# BDAN_ACOND.net
KiCad netlist of a schematic drawn in Altium Designer
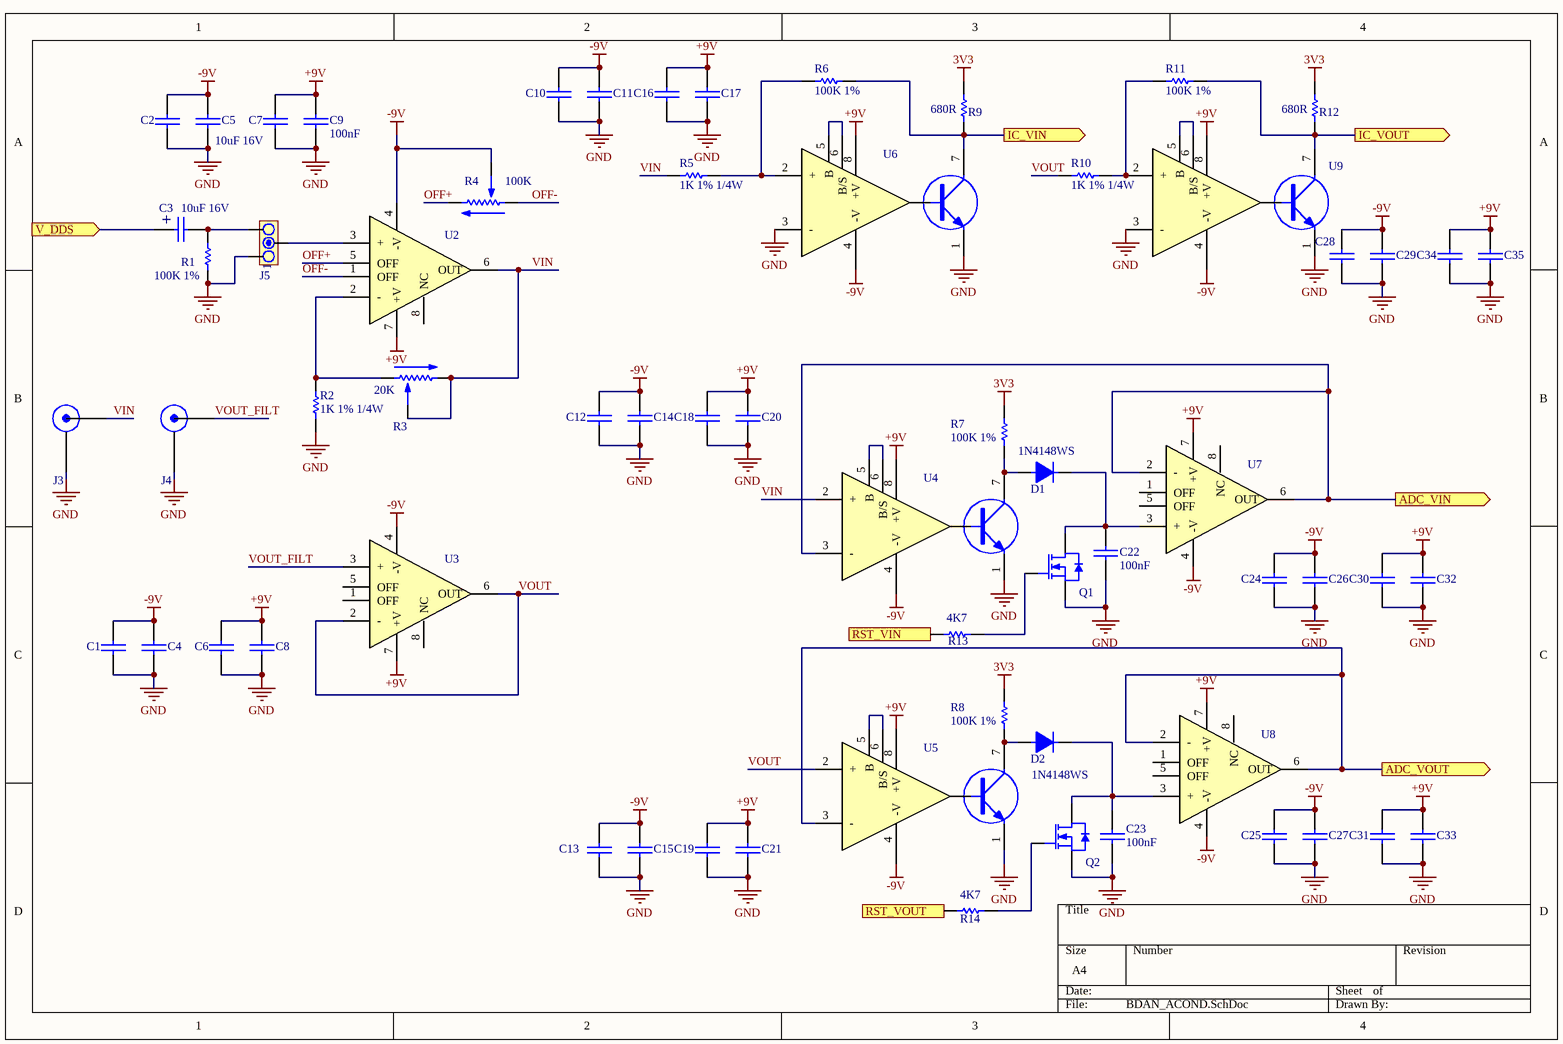
[diagram p0: BDAN_ACOND.SchDoc]

(export (version "E")
  (design (tool "Eeschema 10.0.6"))
  (components
    (comp (ref "C1")
      (value "100nF")
      (footprint "0805")
      (description "CAP0805 100nF X7R")
      (fields (field (name "PART NUMBER") "CAP0805_100nF_X7R"))
      (libsource (lib "gl_LIB") (part "CAP"))
    )
    (comp (ref "C2")
      (value "100nF")
      (footprint "0805")
      (description "CAP0805 100nF X7R")
      (fields (field (name "PART NUMBER") "CAP0805_100nF_X7R"))
      (libsource (lib "gl_LIB") (part "CAP"))
    )
    (comp (ref "C3")
      (value "10uF 16V")
      (footprint "CAP318")
      (description "CAP TANT 10UF 10% 16V RADIAL")
      (fields
        (field (name "PART NUMBER") "CAP_TAN_10uF_16V_CAP318")
        (field (name "MANUFACTURER") "KYOCERA AVX")
      )
      (libsource (lib "gl_LIB") (part "CAPPOL"))
    )
    (comp (ref "C4")
      (value "10uF 16V")
      (footprint "0805")
      (description "CAP0805 10uF 16V X5R")
      (fields
        (field (name "PART NUMBER") "CAP0805_10uF_16V_X5R")
        (field (name "MANUFACTURER") "TDK Corporation")
      )
      (libsource (lib "gl_LIB") (part "CAP"))
    )
    (comp (ref "C5")
      (value "10uF 16V")
      (footprint "0805")
      (description "CAP0805 10uF 16V X5R")
      (fields
        (field (name "PART NUMBER") "CAP0805_10uF_16V_X5R")
        (field (name "MANUFACTURER") "TDK Corporation")
      )
      (libsource (lib "gl_LIB") (part "CAP"))
    )
    (comp (ref "C6")
      (value "10uF 16V")
      (footprint "0805")
      (description "CAP0805 10uF 16V X5R")
      (fields
        (field (name "PART NUMBER") "CAP0805_10uF_16V_X5R")
        (field (name "MANUFACTURER") "TDK Corporation")
      )
      (libsource (lib "gl_LIB") (part "CAP"))
    )
    (comp (ref "C7")
      (value "10uF 16V")
      (footprint "0805")
      (description "CAP0805 10uF 16V X5R")
      (fields
        (field (name "PART NUMBER") "CAP0805_10uF_16V_X5R")
        (field (name "MANUFACTURER") "TDK Corporation")
      )
      (libsource (lib "gl_LIB") (part "CAP"))
    )
    (comp (ref "C8")
      (value "100nF")
      (footprint "0805")
      (description "CAP0805 100nF X7R")
      (fields (field (name "PART NUMBER") "CAP0805_100nF_X7R"))
      (libsource (lib "gl_LIB") (part "CAP"))
    )
    (comp (ref "C9")
      (value "100nF")
      (footprint "0805")
      (description "CAP0805 100nF X7R")
      (fields (field (name "PART NUMBER") "CAP0805_100nF_X7R"))
      (libsource (lib "gl_LIB") (part "CAP"))
    )
    (comp (ref "C10")
      (value "100nF")
      (footprint "0805")
      (description "CAP0805 100nF X7R")
      (fields (field (name "PART NUMBER") "CAP0805_100nF_X7R"))
      (libsource (lib "gl_LIB") (part "CAP"))
    )
    (comp (ref "C11")
      (value "10uF 16V")
      (footprint "0805")
      (description "CAP0805 10uF 16V X5R")
      (fields
        (field (name "PART NUMBER") "CAP0805_10uF_16V_X5R")
        (field (name "MANUFACTURER") "TDK Corporation")
      )
      (libsource (lib "gl_LIB") (part "CAP"))
    )
    (comp (ref "C12")
      (value "100nF")
      (footprint "0805")
      (description "CAP0805 100nF X7R")
      (fields (field (name "PART NUMBER") "CAP0805_100nF_X7R"))
      (libsource (lib "gl_LIB") (part "CAP"))
    )
    (comp (ref "C13")
      (value "100nF")
      (footprint "0805")
      (description "CAP0805 100nF X7R")
      (fields (field (name "PART NUMBER") "CAP0805_100nF_X7R"))
      (libsource (lib "gl_LIB") (part "CAP"))
    )
    (comp (ref "C14")
      (value "10uF 16V")
      (footprint "0805")
      (description "CAP0805 10uF 16V X5R")
      (fields
        (field (name "PART NUMBER") "CAP0805_10uF_16V_X5R")
        (field (name "MANUFACTURER") "TDK Corporation")
      )
      (libsource (lib "gl_LIB") (part "CAP"))
    )
    (comp (ref "C15")
      (value "10uF 16V")
      (footprint "0805")
      (description "CAP0805 10uF 16V X5R")
      (fields
        (field (name "PART NUMBER") "CAP0805_10uF_16V_X5R")
        (field (name "MANUFACTURER") "TDK Corporation")
      )
      (libsource (lib "gl_LIB") (part "CAP"))
    )
    (comp (ref "C16")
      (value "10uF 16V")
      (footprint "0805")
      (description "CAP0805 10uF 16V X5R")
      (fields
        (field (name "PART NUMBER") "CAP0805_10uF_16V_X5R")
        (field (name "MANUFACTURER") "TDK Corporation")
      )
      (libsource (lib "gl_LIB") (part "CAP"))
    )
    (comp (ref "C17")
      (value "100nF")
      (footprint "0805")
      (description "CAP0805 100nF X7R")
      (fields (field (name "PART NUMBER") "CAP0805_100nF_X7R"))
      (libsource (lib "gl_LIB") (part "CAP"))
    )
    (comp (ref "C18")
      (value "10uF 16V")
      (footprint "0805")
      (description "CAP0805 10uF 16V X5R")
      (fields
        (field (name "PART NUMBER") "CAP0805_10uF_16V_X5R")
        (field (name "MANUFACTURER") "TDK Corporation")
      )
      (libsource (lib "gl_LIB") (part "CAP"))
    )
    (comp (ref "C19")
      (value "10uF 16V")
      (footprint "0805")
      (description "CAP0805 10uF 16V X5R")
      (fields
        (field (name "PART NUMBER") "CAP0805_10uF_16V_X5R")
        (field (name "MANUFACTURER") "TDK Corporation")
      )
      (libsource (lib "gl_LIB") (part "CAP"))
    )
    (comp (ref "C20")
      (value "100nF")
      (footprint "0805")
      (description "CAP0805 100nF X7R")
      (fields (field (name "PART NUMBER") "CAP0805_100nF_X7R"))
      (libsource (lib "gl_LIB") (part "CAP"))
    )
    (comp (ref "C21")
      (value "100nF")
      (footprint "0805")
      (description "CAP0805 100nF X7R")
      (fields (field (name "PART NUMBER") "CAP0805_100nF_X7R"))
      (libsource (lib "gl_LIB") (part "CAP"))
    )
    (comp (ref "C22")
      (value "100nF")
      (footprint "CAP508")
      (description "CAP CER RAD 100NF 250V C0G 10%")
      (fields (field (name "PART NUMBER") "CAP_CER_100nF_250V_CAP508"))
      (libsource (lib "gl_LIB") (part "CAP"))
    )
    (comp (ref "C23")
      (value "100nF")
      (footprint "CAP508")
      (description "CAP CER RAD 100NF 250V C0G 10%")
      (fields (field (name "PART NUMBER") "CAP_CER_100nF_250V_CAP508"))
      (libsource (lib "gl_LIB") (part "CAP"))
    )
    (comp (ref "C24")
      (value "100nF")
      (footprint "0805")
      (description "CAP0805 100nF X7R")
      (fields (field (name "PART NUMBER") "CAP0805_100nF_X7R"))
      (libsource (lib "gl_LIB") (part "CAP"))
    )
    (comp (ref "C25")
      (value "100nF")
      (footprint "0805")
      (description "CAP0805 100nF X7R")
      (fields (field (name "PART NUMBER") "CAP0805_100nF_X7R"))
      (libsource (lib "gl_LIB") (part "CAP"))
    )
    (comp (ref "C26")
      (value "10uF 16V")
      (footprint "0805")
      (description "CAP0805 10uF 16V X5R")
      (fields
        (field (name "PART NUMBER") "CAP0805_10uF_16V_X5R")
        (field (name "MANUFACTURER") "TDK Corporation")
      )
      (libsource (lib "gl_LIB") (part "CAP"))
    )
    (comp (ref "C27")
      (value "10uF 16V")
      (footprint "0805")
      (description "CAP0805 10uF 16V X5R")
      (fields
        (field (name "PART NUMBER") "CAP0805_10uF_16V_X5R")
        (field (name "MANUFACTURER") "TDK Corporation")
      )
      (libsource (lib "gl_LIB") (part "CAP"))
    )
    (comp (ref "C28")
      (value "100nF")
      (footprint "0805")
      (description "CAP0805 100nF X7R")
      (fields (field (name "PART NUMBER") "CAP0805_100nF_X7R"))
      (libsource (lib "gl_LIB") (part "CAP"))
    )
    (comp (ref "C29")
      (value "10uF 16V")
      (footprint "0805")
      (description "CAP0805 10uF 16V X5R")
      (fields
        (field (name "PART NUMBER") "CAP0805_10uF_16V_X5R")
        (field (name "MANUFACTURER") "TDK Corporation")
      )
      (libsource (lib "gl_LIB") (part "CAP"))
    )
    (comp (ref "C30")
      (value "10uF 16V")
      (footprint "0805")
      (description "CAP0805 10uF 16V X5R")
      (fields
        (field (name "PART NUMBER") "CAP0805_10uF_16V_X5R")
        (field (name "MANUFACTURER") "TDK Corporation")
      )
      (libsource (lib "gl_LIB") (part "CAP"))
    )
    (comp (ref "C31")
      (value "10uF 16V")
      (footprint "0805")
      (description "CAP0805 10uF 16V X5R")
      (fields
        (field (name "PART NUMBER") "CAP0805_10uF_16V_X5R")
        (field (name "MANUFACTURER") "TDK Corporation")
      )
      (libsource (lib "gl_LIB") (part "CAP"))
    )
    (comp (ref "C32")
      (value "100nF")
      (footprint "0805")
      (description "CAP0805 100nF X7R")
      (fields (field (name "PART NUMBER") "CAP0805_100nF_X7R"))
      (libsource (lib "gl_LIB") (part "CAP"))
    )
    (comp (ref "C33")
      (value "100nF")
      (footprint "0805")
      (description "CAP0805 100nF X7R")
      (fields (field (name "PART NUMBER") "CAP0805_100nF_X7R"))
      (libsource (lib "gl_LIB") (part "CAP"))
    )
    (comp (ref "C34")
      (value "10uF 16V")
      (footprint "0805")
      (description "CAP0805 10uF 16V X5R")
      (fields
        (field (name "PART NUMBER") "CAP0805_10uF_16V_X5R")
        (field (name "MANUFACTURER") "TDK Corporation")
      )
      (libsource (lib "gl_LIB") (part "CAP"))
    )
    (comp (ref "C35")
      (value "100nF")
      (footprint "0805")
      (description "CAP0805 100nF X7R")
      (fields (field (name "PART NUMBER") "CAP0805_100nF_X7R"))
      (libsource (lib "gl_LIB") (part "CAP"))
    )
    (comp (ref "D1")
      (value "1N4148WS")
      (footprint "SOD323F")
      (description "DIODE 75V 150MA SOD323F")
      (fields (field (name "PART NUMBER") "1N4148_SOD323F"))
      (libsource (lib "gl_LIB") (part "DIODO"))
    )
    (comp (ref "D2")
      (value "1N4148WS")
      (footprint "SOD323F")
      (description "DIODE 75V 150MA SOD323F")
      (fields (field (name "PART NUMBER") "1N4148_SOD323F"))
      (libsource (lib "gl_LIB") (part "DIODO"))
    )
    (comp (ref "J3")
      (value "BNC")
      (footprint "BNC")
      (description "CONN BNC RCPT STR 50 OHM PCB")
      (fields (field (name "MANUFACTURER") "Amphenol RF") (field (name "MANUFACTURER PART NUMBER") "112404"))
      (libsource (lib "gl_LIB") (part "BNC"))
    )
    (comp (ref "J4")
      (value "BNC")
      (footprint "BNC")
      (description "CONN BNC RCPT STR 50 OHM PCB")
      (fields (field (name "MANUFACTURER") "Amphenol RF") (field (name "MANUFACTURER PART NUMBER") "112404"))
      (libsource (lib "gl_LIB") (part "BNC"))
    )
    (comp (ref "J5")
      (value "JUMPER3")
      (footprint "JUMPER3")
      (description "TIRA DE PINES 1x3 0.1\" + JUMPER")
      (fields (field (name "PART NUMBER") "JUMPER3_TH") (field (name "MANUFACTURER") "Harwin Inc."))
      (libsource (lib "gl_LIB") (part "JUMPER3"))
    )
    (comp (ref "Q1")
      (value "2N7000")
      (footprint "TO92_DGS")
      (description "MOSFET N-CH 60V 200MA TO-92")
      (fields (field (name "PART NUMBER") "2N7000_TO92"))
      (libsource (lib "gl_LIB") (part "MOSFET N"))
    )
    (comp (ref "Q2")
      (value "2N7000")
      (footprint "TO92_DGS")
      (description "MOSFET N-CH 60V 200MA TO-92")
      (fields (field (name "PART NUMBER") "2N7000_TO92"))
      (libsource (lib "gl_LIB") (part "MOSFET N"))
    )
    (comp (ref "R1")
      (value "100K 1%")
      (footprint "0805")
      (description "RES0805 100K 1%")
      (fields
        (field (name "PART NUMBER") "RES0805_100K_1%")
        (field (name "MANUFACTURER") "Stackpole Electronics Inc")
      )
      (libsource (lib "gl_LIB") (part "RES"))
    )
    (comp (ref "R2")
      (value "1K 1% 1/4W")
      (footprint "0805")
      (description "RES SMD 1K OHM 1% 1/4W 0805")
      (fields
        (field (name "PART NUMBER") "RES0805_1K_1%")
        (field (name "MANUFACTURER") "Stackpole Electronics Inc")
      )
      (libsource (lib "gl_LIB") (part "RES"))
    )
    (comp (ref "R3")
      (value "20K")
      (footprint "3296W-TOP")
      (description "3296 TRIMMER 20K OHM 0.5W PC PIN")
      (fields (field (name "PART NUMBER") "TRIMMER_3296W_20K") (field (name "MANUFACTURER") "Bourns Inc."))
      (libsource (lib "gl_LIB") (part "RESVAR"))
    )
    (comp (ref "R4")
      (value "100K")
      (footprint "3296W-TOP")
      (description "3296 TRIMMER 100K OHM 0.5W PC PIN")
      (fields
        (field (name "PART NUMBER") "TRIMMER_3296W_100K_MULTI")
        (field (name "MANUFACTURER") "Bourns Inc.")
      )
      (libsource (lib "gl_LIB") (part "RESVAR"))
    )
    (comp (ref "R5")
      (value "1K 1% 1/4W")
      (footprint "0805")
      (description "RES SMD 1K OHM 1% 1/4W 0805")
      (fields
        (field (name "PART NUMBER") "RES0805_1K_1%")
        (field (name "MANUFACTURER") "Stackpole Electronics Inc")
      )
      (libsource (lib "gl_LIB") (part "RES"))
    )
    (comp (ref "R6")
      (value "100K 1%")
      (footprint "0805")
      (description "RES0805 100K 1%")
      (fields
        (field (name "PART NUMBER") "RES0805_100K_1%")
        (field (name "MANUFACTURER") "Stackpole Electronics Inc")
      )
      (libsource (lib "gl_LIB") (part "RES"))
    )
    (comp (ref "R7")
      (value "100K 1%")
      (footprint "0805")
      (description "RES0805 100K 1%")
      (fields
        (field (name "PART NUMBER") "RES0805_100K_1%")
        (field (name "MANUFACTURER") "Stackpole Electronics Inc")
      )
      (libsource (lib "gl_LIB") (part "RES"))
    )
    (comp (ref "R8")
      (value "100K 1%")
      (footprint "0805")
      (description "RES0805 100K 1%")
      (fields
        (field (name "PART NUMBER") "RES0805_100K_1%")
        (field (name "MANUFACTURER") "Stackpole Electronics Inc")
      )
      (libsource (lib "gl_LIB") (part "RES"))
    )
    (comp (ref "R9")
      (value "680R")
      (footprint "0805")
      (description "RES0805 680R 1%")
      (fields
        (field (name "PART NUMBER") "RES0805_680R_1%")
        (field (name "MANUFACTURER") "Stackpole Electronics Inc")
      )
      (libsource (lib "gl_LIB") (part "RES"))
    )
    (comp (ref "R10")
      (value "1K 1% 1/4W")
      (footprint "0805")
      (description "RES SMD 1K OHM 1% 1/4W 0805")
      (fields
        (field (name "PART NUMBER") "RES0805_1K_1%")
        (field (name "MANUFACTURER") "Stackpole Electronics Inc")
      )
      (libsource (lib "gl_LIB") (part "RES"))
    )
    (comp (ref "R11")
      (value "100K 1%")
      (footprint "0805")
      (description "RES0805 100K 1%")
      (fields
        (field (name "PART NUMBER") "RES0805_100K_1%")
        (field (name "MANUFACTURER") "Stackpole Electronics Inc")
      )
      (libsource (lib "gl_LIB") (part "RES"))
    )
    (comp (ref "R12")
      (value "680R")
      (footprint "0805")
      (description "RES0805 680R 1%")
      (fields
        (field (name "PART NUMBER") "RES0805_680R_1%")
        (field (name "MANUFACTURER") "Stackpole Electronics Inc")
      )
      (libsource (lib "gl_LIB") (part "RES"))
    )
    (comp (ref "R13")
      (value "4K7")
      (footprint "0805")
      (description "RES0805 4K7 5%")
      (fields
        (field (name "PART NUMBER") "RES0805_4K7_5%")
        (field (name "MANUFACTURER") "Stackpole Electronics Inc")
      )
      (libsource (lib "gl_LIB") (part "RES"))
    )
    (comp (ref "R14")
      (value "4K7")
      (footprint "0805")
      (description "RES0805 4K7 5%")
      (fields
        (field (name "PART NUMBER") "RES0805_4K7_5%")
        (field (name "MANUFACTURER") "Stackpole Electronics Inc")
      )
      (libsource (lib "gl_LIB") (part "RES"))
    )
    (comp (ref "U2")
      (value "OPA604APG4")
      (footprint "DIP8")
      (description "IC OPAMP GP 1 CIRCUIT 8DIP")
      (fields (field (name "MANUFACTURER") "Texas Instruments"))
      (libsource (lib "gl_LIB") (part "OPA604APG4"))
    )
    (comp (ref "U3")
      (value "OPA604APG4")
      (footprint "DIP8")
      (description "IC OPAMP GP 1 CIRCUIT 8DIP")
      (fields (field (name "MANUFACTURER") "Texas Instruments"))
      (libsource (lib "gl_LIB") (part "OPA604APG4"))
    )
    (comp (ref "U4")
      (value "LM311M")
      (footprint "DIP8")
      (description "IC VOLTAGE COMPARATOR 8-SOIC")
      (fields (field (name "PART NUMBER") "LM311N"))
      (libsource (lib "gl_LIB") (part "LM311_N"))
    )
    (comp (ref "U5")
      (value "LM311M")
      (footprint "DIP8")
      (description "IC VOLTAGE COMPARATOR 8-SOIC")
      (fields (field (name "PART NUMBER") "LM311N"))
      (libsource (lib "gl_LIB") (part "LM311_N"))
    )
    (comp (ref "U6")
      (value "LM311M")
      (footprint "DIP8")
      (description "IC VOLTAGE COMPARATOR 8-SOIC")
      (fields (field (name "PART NUMBER") "LM311N"))
      (libsource (lib "gl_LIB") (part "LM311_N"))
    )
    (comp (ref "U7")
      (value "OPA604APG4")
      (footprint "DIP8")
      (description "IC OPAMP GP 1 CIRCUIT 8DIP")
      (fields (field (name "MANUFACTURER") "Texas Instruments"))
      (libsource (lib "gl_LIB") (part "OPA604APG4"))
    )
    (comp (ref "U8")
      (value "OPA604APG4")
      (footprint "DIP8")
      (description "IC OPAMP GP 1 CIRCUIT 8DIP")
      (fields (field (name "MANUFACTURER") "Texas Instruments"))
      (libsource (lib "gl_LIB") (part "OPA604APG4"))
    )
    (comp (ref "U9")
      (value "LM311M")
      (footprint "DIP8")
      (description "IC VOLTAGE COMPARATOR 8-SOIC")
      (fields (field (name "PART NUMBER") "LM311N"))
      (libsource (lib "gl_LIB") (part "LM311_N"))
    )
  )
  (nets
    (net (code "1") (name "+9V") (class "Default")
      (node (ref "C16") (pin "1") (pinfunction "1_1") (pintype "passive"))
      (node (ref "C17") (pin "1") (pinfunction "1_1") (pintype "passive"))
      (node (ref "C18") (pin "1") (pinfunction "1_1") (pintype "passive"))
      (node (ref "C19") (pin "1") (pinfunction "1_1") (pintype "passive"))
      (node (ref "C20") (pin "1") (pinfunction "1_1") (pintype "passive"))
      (node (ref "C21") (pin "1") (pinfunction "1_1") (pintype "passive"))
      (node (ref "C30") (pin "1") (pinfunction "1_1") (pintype "passive"))
      (node (ref "C31") (pin "1") (pinfunction "1_1") (pintype "passive"))
      (node (ref "C32") (pin "1") (pinfunction "1_1") (pintype "passive"))
      (node (ref "C33") (pin "1") (pinfunction "1_1") (pintype "passive"))
      (node (ref "C34") (pin "1") (pinfunction "1_1") (pintype "passive"))
      (node (ref "C35") (pin "1") (pinfunction "1_1") (pintype "passive"))
      (node (ref "C6") (pin "1") (pinfunction "1_1") (pintype "passive"))
      (node (ref "C7") (pin "1") (pinfunction "1_1") (pintype "passive"))
      (node (ref "C8") (pin "1") (pinfunction "1_1") (pintype "passive"))
      (node (ref "C9") (pin "1") (pinfunction "1_1") (pintype "passive"))
      (node (ref "U2") (pin "7") (pinfunction "+V_7") (pintype "passive"))
      (node (ref "U3") (pin "7") (pinfunction "+V_7") (pintype "passive"))
      (node (ref "U4") (pin "8") (pinfunction "+V_8") (pintype "passive"))
      (node (ref "U5") (pin "8") (pinfunction "+V_8") (pintype "passive"))
      (node (ref "U6") (pin "8") (pinfunction "+V_8") (pintype "passive"))
      (node (ref "U7") (pin "7") (pinfunction "+V_7") (pintype "passive"))
      (node (ref "U8") (pin "7") (pinfunction "+V_7") (pintype "passive"))
      (node (ref "U9") (pin "8") (pinfunction "+V_8") (pintype "passive"))
    )
    (net (code "2") (name "-9V") (class "Default")
      (node (ref "C1") (pin "1") (pinfunction "1_1") (pintype "passive"))
      (node (ref "C10") (pin "1") (pinfunction "1_1") (pintype "passive"))
      (node (ref "C11") (pin "1") (pinfunction "1_1") (pintype "passive"))
      (node (ref "C12") (pin "1") (pinfunction "1_1") (pintype "passive"))
      (node (ref "C13") (pin "1") (pinfunction "1_1") (pintype "passive"))
      (node (ref "C14") (pin "1") (pinfunction "1_1") (pintype "passive"))
      (node (ref "C15") (pin "1") (pinfunction "1_1") (pintype "passive"))
      (node (ref "C2") (pin "1") (pinfunction "1_1") (pintype "passive"))
      (node (ref "C24") (pin "1") (pinfunction "1_1") (pintype "passive"))
      (node (ref "C25") (pin "1") (pinfunction "1_1") (pintype "passive"))
      (node (ref "C26") (pin "1") (pinfunction "1_1") (pintype "passive"))
      (node (ref "C27") (pin "1") (pinfunction "1_1") (pintype "passive"))
      (node (ref "C28") (pin "1") (pinfunction "1_1") (pintype "passive"))
      (node (ref "C29") (pin "1") (pinfunction "1_1") (pintype "passive"))
      (node (ref "C4") (pin "1") (pinfunction "1_1") (pintype "passive"))
      (node (ref "C5") (pin "1") (pinfunction "1_1") (pintype "passive"))
      (node (ref "R4") (pin "2") (pinfunction "WIPER_2") (pintype "passive"))
      (node (ref "U2") (pin "4") (pinfunction "-V_4") (pintype "passive"))
      (node (ref "U3") (pin "4") (pinfunction "-V_4") (pintype "passive"))
      (node (ref "U4") (pin "4") (pinfunction "-V_4") (pintype "passive"))
      (node (ref "U5") (pin "4") (pinfunction "-V_4") (pintype "passive"))
      (node (ref "U6") (pin "4") (pinfunction "-V_4") (pintype "passive"))
      (node (ref "U7") (pin "4") (pinfunction "-V_4") (pintype "passive"))
      (node (ref "U8") (pin "4") (pinfunction "-V_4") (pintype "passive"))
      (node (ref "U9") (pin "4") (pinfunction "-V_4") (pintype "passive"))
    )
    (net (code "3") (name "/ADC_VIN") (class "Default")
      (node (ref "U4") (pin "3") (pinfunction "-_3") (pintype "passive"))
      (node (ref "U7") (pin "2") (pinfunction "-_2") (pintype "passive"))
      (node (ref "U7") (pin "6") (pinfunction "OUT_6") (pintype "passive"))
    )
    (net (code "4") (name "/ADC_VOUT") (class "Default")
      (node (ref "U5") (pin "3") (pinfunction "-_3") (pintype "passive"))
      (node (ref "U8") (pin "2") (pinfunction "-_2") (pintype "passive"))
      (node (ref "U8") (pin "6") (pinfunction "OUT_6") (pintype "passive"))
    )
    (net (code "5") (name "/IC_VIN") (class "Default")
      (node (ref "R6") (pin "1") (pinfunction "1_1") (pintype "passive"))
      (node (ref "R9") (pin "1") (pinfunction "1_1") (pintype "passive"))
      (node (ref "U6") (pin "7") (pinfunction "COL_OUT_7") (pintype "passive"))
    )
    (net (code "6") (name "/IC_VOUT") (class "Default")
      (node (ref "R11") (pin "1") (pinfunction "1_1") (pintype "passive"))
      (node (ref "R12") (pin "1") (pinfunction "1_1") (pintype "passive"))
      (node (ref "U9") (pin "7") (pinfunction "COL_OUT_7") (pintype "passive"))
    )
    (net (code "7") (name "/OFF+") (class "Default")
      (node (ref "R4") (pin "3") (pinfunction "CW_3") (pintype "passive"))
      (node (ref "U2") (pin "5") (pinfunction "OFF_5") (pintype "passive"))
    )
    (net (code "8") (name "/OFF-") (class "Default")
      (node (ref "R4") (pin "1") (pinfunction "CCW_1") (pintype "passive"))
      (node (ref "U2") (pin "1") (pinfunction "OFF_1") (pintype "passive"))
    )
    (net (code "9") (name "/RST_VIN") (class "Default")
      (node (ref "R13") (pin "1") (pinfunction "1_1") (pintype "passive"))
    )
    (net (code "10") (name "/RST_VOUT") (class "Default")
      (node (ref "R14") (pin "1") (pinfunction "1_1") (pintype "passive"))
    )
    (net (code "11") (name "/VIN") (class "Default")
      (node (ref "J3") (pin "2") (pinfunction "2_2") (pintype "passive"))
      (node (ref "R3") (pin "2") (pinfunction "WIPER_2") (pintype "passive"))
      (node (ref "R3") (pin "3") (pinfunction "CW_3") (pintype "passive"))
      (node (ref "R5") (pin "2") (pinfunction "2_2") (pintype "passive"))
      (node (ref "U2") (pin "6") (pinfunction "OUT_6") (pintype "passive"))
      (node (ref "U4") (pin "2") (pinfunction "+_2") (pintype "passive"))
    )
    (net (code "12") (name "/VOUT") (class "Default")
      (node (ref "R10") (pin "2") (pinfunction "2_2") (pintype "passive"))
      (node (ref "U3") (pin "2") (pinfunction "-_2") (pintype "passive"))
      (node (ref "U3") (pin "6") (pinfunction "OUT_6") (pintype "passive"))
      (node (ref "U5") (pin "2") (pinfunction "+_2") (pintype "passive"))
    )
    (net (code "13") (name "/VOUT_FILT") (class "Default")
      (node (ref "J4") (pin "2") (pinfunction "2_2") (pintype "passive"))
      (node (ref "U3") (pin "3") (pinfunction "+_3") (pintype "passive"))
    )
    (net (code "14") (name "/V_DDS") (class "Default")
      (node (ref "C3") (pin "1") (pinfunction "1_1") (pintype "passive"))
    )
    (net (code "15") (name "3V3") (class "Default")
      (node (ref "R12") (pin "2") (pinfunction "2_2") (pintype "passive"))
      (node (ref "R7") (pin "2") (pinfunction "2_2") (pintype "passive"))
      (node (ref "R8") (pin "2") (pinfunction "2_2") (pintype "passive"))
      (node (ref "R9") (pin "2") (pinfunction "2_2") (pintype "passive"))
    )
    (net (code "16") (name "GND") (class "Default")
      (node (ref "C1") (pin "2") (pinfunction "2_2") (pintype "passive"))
      (node (ref "C10") (pin "2") (pinfunction "2_2") (pintype "passive"))
      (node (ref "C11") (pin "2") (pinfunction "2_2") (pintype "passive"))
      (node (ref "C12") (pin "2") (pinfunction "2_2") (pintype "passive"))
      (node (ref "C13") (pin "2") (pinfunction "2_2") (pintype "passive"))
      (node (ref "C14") (pin "2") (pinfunction "2_2") (pintype "passive"))
      (node (ref "C15") (pin "2") (pinfunction "2_2") (pintype "passive"))
      (node (ref "C16") (pin "2") (pinfunction "2_2") (pintype "passive"))
      (node (ref "C17") (pin "2") (pinfunction "2_2") (pintype "passive"))
      (node (ref "C18") (pin "2") (pinfunction "2_2") (pintype "passive"))
      (node (ref "C19") (pin "2") (pinfunction "2_2") (pintype "passive"))
      (node (ref "C2") (pin "2") (pinfunction "2_2") (pintype "passive"))
      (node (ref "C20") (pin "2") (pinfunction "2_2") (pintype "passive"))
      (node (ref "C21") (pin "2") (pinfunction "2_2") (pintype "passive"))
      (node (ref "C22") (pin "2") (pinfunction "2_2") (pintype "passive"))
      (node (ref "C23") (pin "2") (pinfunction "2_2") (pintype "passive"))
      (node (ref "C24") (pin "2") (pinfunction "2_2") (pintype "passive"))
      (node (ref "C25") (pin "2") (pinfunction "2_2") (pintype "passive"))
      (node (ref "C26") (pin "2") (pinfunction "2_2") (pintype "passive"))
      (node (ref "C27") (pin "2") (pinfunction "2_2") (pintype "passive"))
      (node (ref "C28") (pin "2") (pinfunction "2_2") (pintype "passive"))
      (node (ref "C29") (pin "2") (pinfunction "2_2") (pintype "passive"))
      (node (ref "C30") (pin "2") (pinfunction "2_2") (pintype "passive"))
      (node (ref "C31") (pin "2") (pinfunction "2_2") (pintype "passive"))
      (node (ref "C32") (pin "2") (pinfunction "2_2") (pintype "passive"))
      (node (ref "C33") (pin "2") (pinfunction "2_2") (pintype "passive"))
      (node (ref "C34") (pin "2") (pinfunction "2_2") (pintype "passive"))
      (node (ref "C35") (pin "2") (pinfunction "2_2") (pintype "passive"))
      (node (ref "C4") (pin "2") (pinfunction "2_2") (pintype "passive"))
      (node (ref "C5") (pin "2") (pinfunction "2_2") (pintype "passive"))
      (node (ref "C6") (pin "2") (pinfunction "2_2") (pintype "passive"))
      (node (ref "C7") (pin "2") (pinfunction "2_2") (pintype "passive"))
      (node (ref "C8") (pin "2") (pinfunction "2_2") (pintype "passive"))
      (node (ref "C9") (pin "2") (pinfunction "2_2") (pintype "passive"))
      (node (ref "J3") (pin "1") (pinfunction "1_1") (pintype "passive"))
      (node (ref "J4") (pin "1") (pinfunction "1_1") (pintype "passive"))
      (node (ref "J5") (pin "1") (pinfunction "1_1") (pintype "passive"))
      (node (ref "Q1") (pin "3") (pinfunction "S_3") (pintype "passive"))
      (node (ref "Q2") (pin "3") (pinfunction "S_3") (pintype "passive"))
      (node (ref "R1") (pin "1") (pinfunction "1_1") (pintype "passive"))
      (node (ref "R2") (pin "1") (pinfunction "1_1") (pintype "passive"))
      (node (ref "U4") (pin "1") (pinfunction "EMIT_OUT_1") (pintype "passive"))
      (node (ref "U5") (pin "1") (pinfunction "EMIT_OUT_1") (pintype "passive"))
      (node (ref "U6") (pin "1") (pinfunction "EMIT_OUT_1") (pintype "passive"))
      (node (ref "U6") (pin "3") (pinfunction "-_3") (pintype "passive"))
      (node (ref "U9") (pin "1") (pinfunction "EMIT_OUT_1") (pintype "passive"))
      (node (ref "U9") (pin "3") (pinfunction "-_3") (pintype "passive"))
    )
    (net (code "17") (name "Net-(C3-Pad2)") (class "Default")
      (node (ref "C3") (pin "2") (pinfunction "2_2") (pintype "passive"))
      (node (ref "J5") (pin "3") (pinfunction "3_3") (pintype "passive"))
      (node (ref "R1") (pin "2") (pinfunction "2_2") (pintype "passive"))
    )
    (net (code "18") (name "Net-(Q1-D)") (class "Default")
      (node (ref "C22") (pin "1") (pinfunction "1_1") (pintype "passive"))
      (node (ref "D1") (pin "2") (pinfunction "2_2") (pintype "passive"))
      (node (ref "Q1") (pin "2") (pinfunction "D_2") (pintype "passive"))
      (node (ref "U7") (pin "3") (pinfunction "+_3") (pintype "passive"))
    )
    (net (code "19") (name "Net-(Q1-G)") (class "Default")
      (node (ref "Q1") (pin "1") (pinfunction "G_1") (pintype "passive"))
      (node (ref "R13") (pin "2") (pinfunction "2_2") (pintype "passive"))
    )
    (net (code "20") (name "Net-(Q2-D)") (class "Default")
      (node (ref "C23") (pin "1") (pinfunction "1_1") (pintype "passive"))
      (node (ref "D2") (pin "2") (pinfunction "2_2") (pintype "passive"))
      (node (ref "Q2") (pin "2") (pinfunction "D_2") (pintype "passive"))
      (node (ref "U8") (pin "3") (pinfunction "+_3") (pintype "passive"))
    )
    (net (code "21") (name "Net-(Q2-G)") (class "Default")
      (node (ref "Q2") (pin "1") (pinfunction "G_1") (pintype "passive"))
      (node (ref "R14") (pin "2") (pinfunction "2_2") (pintype "passive"))
    )
    (net (code "22") (name "Net-(R3-CCW)") (class "Default")
      (node (ref "R2") (pin "2") (pinfunction "2_2") (pintype "passive"))
      (node (ref "R3") (pin "1") (pinfunction "CCW_1") (pintype "passive"))
      (node (ref "U2") (pin "2") (pinfunction "-_2") (pintype "passive"))
    )
    (net (code "23") (name "Net-(U2-+)") (class "Default")
      (node (ref "J5") (pin "2") (pinfunction "2_2") (pintype "passive"))
      (node (ref "U2") (pin "3") (pinfunction "+_3") (pintype "passive"))
    )
    (net (code "24") (name "Net-(U4-B)") (class "Default")
      (node (ref "U4") (pin "5") (pinfunction "B_5") (pintype "passive"))
      (node (ref "U4") (pin "6") (pinfunction "B/S_6") (pintype "passive"))
    )
    (net (code "25") (name "Net-(U4-COL_OUT)") (class "Default")
      (node (ref "D1") (pin "1") (pinfunction "1_1") (pintype "passive"))
      (node (ref "R7") (pin "1") (pinfunction "1_1") (pintype "passive"))
      (node (ref "U4") (pin "7") (pinfunction "COL_OUT_7") (pintype "passive"))
    )
    (net (code "26") (name "Net-(U5-B)") (class "Default")
      (node (ref "U5") (pin "5") (pinfunction "B_5") (pintype "passive"))
      (node (ref "U5") (pin "6") (pinfunction "B/S_6") (pintype "passive"))
    )
    (net (code "27") (name "Net-(U5-COL_OUT)") (class "Default")
      (node (ref "D2") (pin "1") (pinfunction "1_1") (pintype "passive"))
      (node (ref "R8") (pin "1") (pinfunction "1_1") (pintype "passive"))
      (node (ref "U5") (pin "7") (pinfunction "COL_OUT_7") (pintype "passive"))
    )
    (net (code "28") (name "Net-(U6-+)") (class "Default")
      (node (ref "R5") (pin "1") (pinfunction "1_1") (pintype "passive"))
      (node (ref "R6") (pin "2") (pinfunction "2_2") (pintype "passive"))
      (node (ref "U6") (pin "2") (pinfunction "+_2") (pintype "passive"))
    )
    (net (code "29") (name "Net-(U6-B)") (class "Default")
      (node (ref "U6") (pin "5") (pinfunction "B_5") (pintype "passive"))
      (node (ref "U6") (pin "6") (pinfunction "B/S_6") (pintype "passive"))
    )
    (net (code "30") (name "Net-(U9-+)") (class "Default")
      (node (ref "R10") (pin "1") (pinfunction "1_1") (pintype "passive"))
      (node (ref "R11") (pin "2") (pinfunction "2_2") (pintype "passive"))
      (node (ref "U9") (pin "2") (pinfunction "+_2") (pintype "passive"))
    )
    (net (code "31") (name "Net-(U9-B)") (class "Default")
      (node (ref "U9") (pin "5") (pinfunction "B_5") (pintype "passive"))
      (node (ref "U9") (pin "6") (pinfunction "B/S_6") (pintype "passive"))
    )
    (net (code "32") (name "unconnected-(U2-NC-Pad8)") (class "Default")
      (node (ref "U2") (pin "8") (pinfunction "NC_8") (pintype "passive"))
    )
    (net (code "33") (name "unconnected-(U3-NC-Pad8)") (class "Default")
      (node (ref "U3") (pin "8") (pinfunction "NC_8") (pintype "passive"))
    )
    (net (code "34") (name "unconnected-(U3-OFF-Pad1)") (class "Default")
      (node (ref "U3") (pin "1") (pinfunction "OFF_1") (pintype "passive"))
    )
    (net (code "35") (name "unconnected-(U3-OFF-Pad5)") (class "Default")
      (node (ref "U3") (pin "5") (pinfunction "OFF_5") (pintype "passive"))
    )
    (net (code "36") (name "unconnected-(U7-NC-Pad8)") (class "Default")
      (node (ref "U7") (pin "8") (pinfunction "NC_8") (pintype "passive"))
    )
    (net (code "37") (name "unconnected-(U7-OFF-Pad1)") (class "Default")
      (node (ref "U7") (pin "1") (pinfunction "OFF_1") (pintype "passive"))
    )
    (net (code "38") (name "unconnected-(U7-OFF-Pad5)") (class "Default")
      (node (ref "U7") (pin "5") (pinfunction "OFF_5") (pintype "passive"))
    )
    (net (code "39") (name "unconnected-(U8-NC-Pad8)") (class "Default")
      (node (ref "U8") (pin "8") (pinfunction "NC_8") (pintype "passive"))
    )
    (net (code "40") (name "unconnected-(U8-OFF-Pad1)") (class "Default")
      (node (ref "U8") (pin "1") (pinfunction "OFF_1") (pintype "passive"))
    )
    (net (code "41") (name "unconnected-(U8-OFF-Pad5)") (class "Default")
      (node (ref "U8") (pin "5") (pinfunction "OFF_5") (pintype "passive"))
    )
  )
)
